# MODULO_GPS.net
KiCad netlist of a schematic drawn in EAGLE
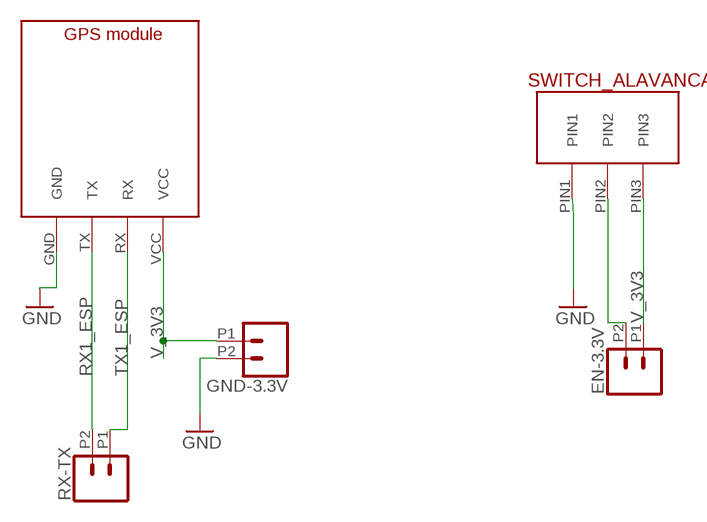
[diagram p0: schematic, sheet 1]

(export (version "E")
  (design (tool "Eeschema 10.0.6"))
  (components
    (comp (ref "EN-3.3V")
      (value "CONN_022.54MM_SCREWTERM")
      (footprint "eagle-import:1X02_2.54_SCREWTERM")
      (libsource (lib "eagle-import") (part "CONN_022.54MM_SCREWTERM"))
    )
    (comp (ref "GND-3.3V")
      (value "CONN_022.54MM_SCREWTERM")
      (footprint "eagle-import:1X02_2.54_SCREWTERM")
      (libsource (lib "eagle-import") (part "CONN_022.54MM_SCREWTERM"))
    )
    (comp (ref "RX-TX")
      (value "CONN_022.54MM_SCREWTERM")
      (footprint "eagle-import:1X02_2.54_SCREWTERM")
      (libsource (lib "eagle-import") (part "CONN_022.54MM_SCREWTERM"))
    )
    (comp (ref "U$1")
      (value "SWITCH_ALAVANCA")
      (footprint "eagle-import:SWITCH_ALAVANCA_FOOTPRINT")
      (libsource (lib "eagle-import") (part "SWITCH_ALAVANCA"))
    )
    (comp (ref "U$3")
      (value "GPS_MODULE")
      (footprint "eagle-import:GPS_MODULE_FOOTPRINT")
      (libsource (lib "eagle-import") (part "GPS_MODULE"))
    )
  )
  (nets
    (net (code "1") (name "/RX1_ESP") (class "Default")
      (node (ref "RX-TX") (pin "P2") (pinfunction "2_P2") (pintype "passive"))
      (node (ref "U$3") (pin "TX") (pinfunction "TX_TX") (pintype "bidirectional"))
    )
    (net (code "2") (name "/TX1_ESP") (class "Default")
      (node (ref "RX-TX") (pin "P1") (pinfunction "1_P1") (pintype "passive"))
      (node (ref "U$3") (pin "RX") (pinfunction "RX_RX") (pintype "bidirectional"))
    )
    (net (code "3") (name "/V_3V3") (class "Default")
      (node (ref "EN-3.3V") (pin "P1") (pinfunction "1_P1") (pintype "passive"))
      (node (ref "GND-3.3V") (pin "P1") (pinfunction "1_P1") (pintype "passive"))
      (node (ref "U$1") (pin "PIN3") (pinfunction "PIN3_PIN3") (pintype "bidirectional"))
      (node (ref "U$3") (pin "VCC") (pinfunction "VCC_VCC") (pintype "bidirectional"))
    )
    (net (code "4") (name "GND") (class "Default")
      (node (ref "GND-3.3V") (pin "P2") (pinfunction "2_P2") (pintype "passive"))
      (node (ref "U$1") (pin "PIN1") (pinfunction "PIN1_PIN1") (pintype "bidirectional"))
      (node (ref "U$3") (pin "GND") (pinfunction "GND_GND") (pintype "bidirectional"))
    )
    (net (code "5") (name "Net-(EN-3.3V-2)") (class "Default")
      (node (ref "EN-3.3V") (pin "P2") (pinfunction "2_P2") (pintype "passive"))
      (node (ref "U$1") (pin "PIN2") (pinfunction "PIN2_PIN2") (pintype "bidirectional"))
    )
  )
)
